# 453_mic.net
KiCad netlist of a schematic drawn in EAGLE
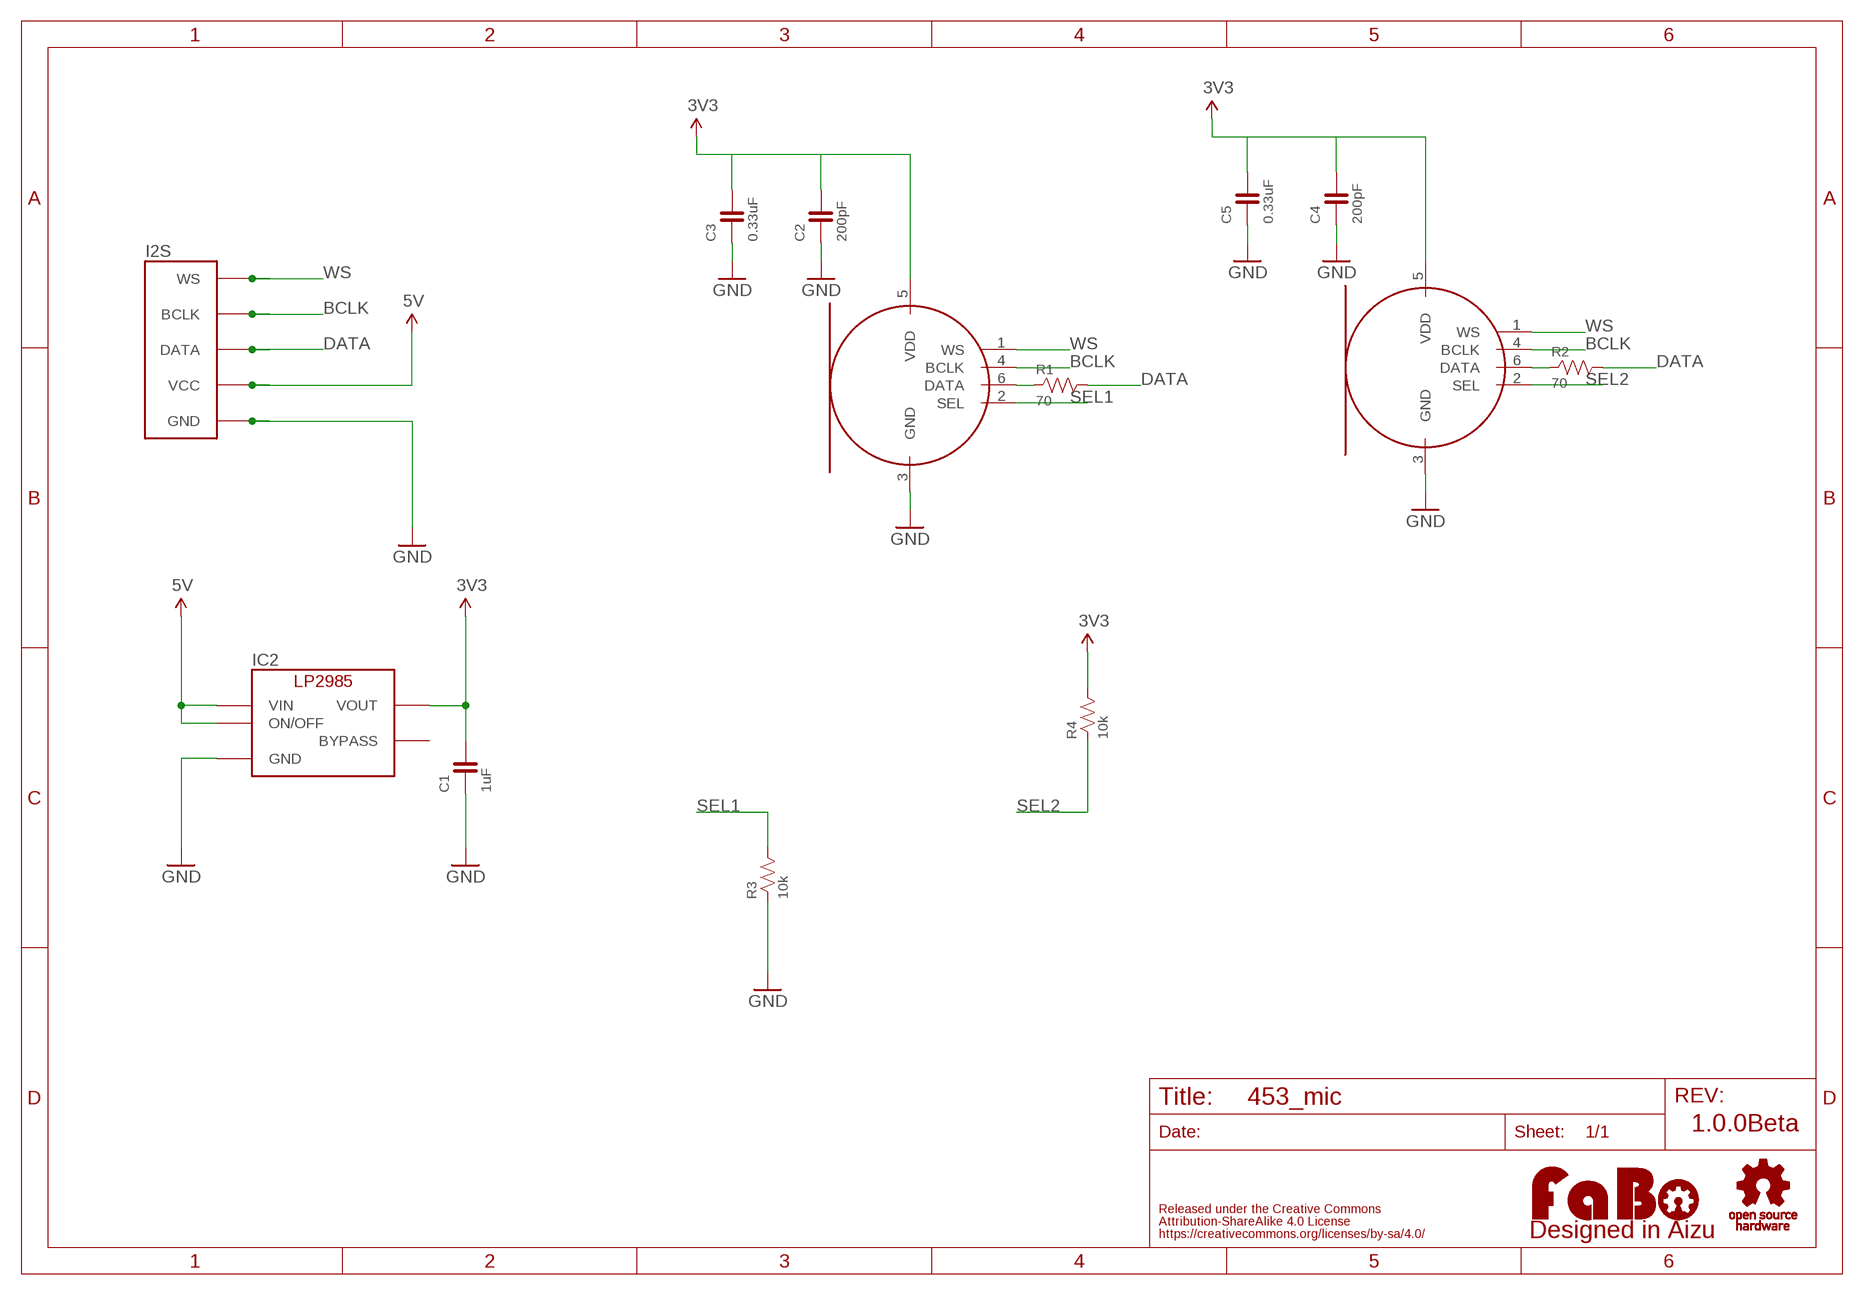
[diagram p0: schematic, sheet 1]

(export (version "E")
  (design (tool "Eeschema 10.0.6"))
  (components
    (comp (ref "C1")
      (value "1uF")
      (footprint "eagle-import:0603")
      (libsource (lib "eagle-import") (part "CAPACITOR-0603"))
    )
    (comp (ref "C2")
      (value "200pF")
      (footprint "eagle-import:0603")
      (libsource (lib "eagle-import") (part "CAPACITOR-0603"))
    )
    (comp (ref "C3")
      (value "0.33uF")
      (footprint "eagle-import:0603")
      (libsource (lib "eagle-import") (part "CAPACITOR-0603"))
    )
    (comp (ref "C4")
      (value "200pF")
      (footprint "eagle-import:0603")
      (libsource (lib "eagle-import") (part "CAPACITOR-0603"))
    )
    (comp (ref "C5")
      (value "0.33uF")
      (footprint "eagle-import:0603")
      (libsource (lib "eagle-import") (part "CAPACITOR-0603"))
    )
    (comp (ref "I2S")
      (value "FABO_BRICK_I2STOP")
      (footprint "eagle-import:FABO_BRICK_I2S_B05B-PARK-1")
      (libsource (lib "eagle-import") (part "FABO_BRICK_I2STOP"))
    )
    (comp (ref "IC2")
      (value "LP2985-33DBV")
      (footprint "eagle-import:SOT-23-5")
      (libsource (lib "eagle-import") (part "LP2985-33DBV"))
    )
    (comp (ref "LOGO1")
      (value "LOGO_FABO-M_BOTTOM")
      (footprint "eagle-import:LOGO_FABO_M_BOTTOM")
      (libsource (lib "eagle-import") (part "LOGO_FABO-M_BOTTOM"))
    )
    (comp (ref "MIC1")
      (value "KW-SPH0645")
      (footprint "eagle-import:KNOWLES-SPH0645")
      (libsource (lib "eagle-import") (part "KW-SPH0645"))
    )
    (comp (ref "MIC2")
      (value "KW-SPH0645")
      (footprint "eagle-import:KNOWLES-SPH0645")
      (libsource (lib "eagle-import") (part "KW-SPH0645"))
    )
    (comp (ref "R1")
      (value "70")
      (footprint "eagle-import:0603")
      (libsource (lib "eagle-import") (part "RESISTOR-0603"))
    )
    (comp (ref "R2")
      (value "70")
      (footprint "eagle-import:0603")
      (libsource (lib "eagle-import") (part "RESISTOR-0603"))
    )
    (comp (ref "R3")
      (value "10k")
      (footprint "eagle-import:0603")
      (libsource (lib "eagle-import") (part "RESISTOR-0603"))
    )
    (comp (ref "R4")
      (value "10k")
      (footprint "eagle-import:0603")
      (libsource (lib "eagle-import") (part "RESISTOR-0603"))
    )
    (comp (ref "U$2")
      (value "LOGO_OSHW-M")
      (footprint "eagle-import:LOGO_OSHW_M")
      (libsource (lib "eagle-import") (part "LOGO_OSHW-M"))
    )
  )
  (nets
    (net (code "1") (name "/BCLK") (class "Default")
      (node (ref "I2S") (pin "BCLK") (pinfunction "BCLK_BCLK") (pintype "bidirectional"))
      (node (ref "MIC1") (pin "4") (pinfunction "BCLK_4") (pintype "bidirectional"))
      (node (ref "MIC2") (pin "4") (pinfunction "BCLK_4") (pintype "bidirectional"))
    )
    (net (code "2") (name "/DATA") (class "Default")
      (node (ref "I2S") (pin "DATA") (pinfunction "DATA_DATA") (pintype "bidirectional"))
      (node (ref "R1") (pin "2") (pinfunction "2_2") (pintype "bidirectional"))
      (node (ref "R2") (pin "2") (pinfunction "2_2") (pintype "bidirectional"))
    )
    (net (code "3") (name "/SEL1") (class "Default")
      (node (ref "MIC1") (pin "2") (pinfunction "SEL_2") (pintype "bidirectional"))
      (node (ref "R3") (pin "2") (pinfunction "2_2") (pintype "bidirectional"))
    )
    (net (code "4") (name "/SEL2") (class "Default")
      (node (ref "MIC2") (pin "2") (pinfunction "SEL_2") (pintype "bidirectional"))
      (node (ref "R4") (pin "1") (pinfunction "1_1") (pintype "bidirectional"))
    )
    (net (code "5") (name "/WS") (class "Default")
      (node (ref "I2S") (pin "WS") (pinfunction "WS_WS") (pintype "bidirectional"))
      (node (ref "MIC1") (pin "1") (pinfunction "WS_1") (pintype "bidirectional"))
      (node (ref "MIC2") (pin "1") (pinfunction "WS_1") (pintype "bidirectional"))
    )
    (net (code "6") (name "3V3") (class "Default")
      (node (ref "C1") (pin "2") (pinfunction "2_2") (pintype "passive"))
      (node (ref "C2") (pin "2") (pinfunction "2_2") (pintype "passive"))
      (node (ref "C3") (pin "2") (pinfunction "2_2") (pintype "passive"))
      (node (ref "C4") (pin "2") (pinfunction "2_2") (pintype "passive"))
      (node (ref "C5") (pin "2") (pinfunction "2_2") (pintype "passive"))
      (node (ref "IC2") (pin "5") (pinfunction "VOUT_5") (pintype "output"))
      (node (ref "MIC1") (pin "5") (pinfunction "VDD_5") (pintype "bidirectional"))
      (node (ref "MIC2") (pin "5") (pinfunction "VDD_5") (pintype "bidirectional"))
      (node (ref "R4") (pin "2") (pinfunction "2_2") (pintype "bidirectional"))
    )
    (net (code "7") (name "5V") (class "Default")
      (node (ref "I2S") (pin "VCC") (pinfunction "VCC_VCC") (pintype "bidirectional"))
      (node (ref "IC2") (pin "1") (pinfunction "VIN_1") (pintype "input"))
      (node (ref "IC2") (pin "3") (pinfunction "ON/OFF_3") (pintype "input"))
    )
    (net (code "8") (name "GND") (class "Default")
      (node (ref "C1") (pin "1") (pinfunction "1_1") (pintype "passive"))
      (node (ref "C2") (pin "1") (pinfunction "1_1") (pintype "passive"))
      (node (ref "C3") (pin "1") (pinfunction "1_1") (pintype "passive"))
      (node (ref "C4") (pin "1") (pinfunction "1_1") (pintype "passive"))
      (node (ref "C5") (pin "1") (pinfunction "1_1") (pintype "passive"))
      (node (ref "I2S") (pin "GND") (pinfunction "GND_GND") (pintype "bidirectional"))
      (node (ref "IC2") (pin "2") (pinfunction "GND_2") (pintype "power_in"))
      (node (ref "MIC1") (pin "3") (pinfunction "GND_3") (pintype "bidirectional"))
      (node (ref "MIC2") (pin "3") (pinfunction "GND_3") (pintype "bidirectional"))
      (node (ref "R3") (pin "1") (pinfunction "1_1") (pintype "bidirectional"))
    )
    (net (code "9") (name "Net-(MIC1-DATA)") (class "Default")
      (node (ref "MIC1") (pin "6") (pinfunction "DATA_6") (pintype "bidirectional"))
      (node (ref "R1") (pin "1") (pinfunction "1_1") (pintype "bidirectional"))
    )
    (net (code "10") (name "Net-(MIC2-DATA)") (class "Default")
      (node (ref "MIC2") (pin "6") (pinfunction "DATA_6") (pintype "bidirectional"))
      (node (ref "R2") (pin "1") (pinfunction "1_1") (pintype "bidirectional"))
    )
    (net (code "11") (name "unconnected-(IC2-BYPASS-Pad4)") (class "Default")
      (node (ref "IC2") (pin "4") (pinfunction "BYPASS_4") (pintype "bidirectional"))
    )
  )
)
